# POWER.net
KiCad netlist of a schematic drawn in Altium Designer
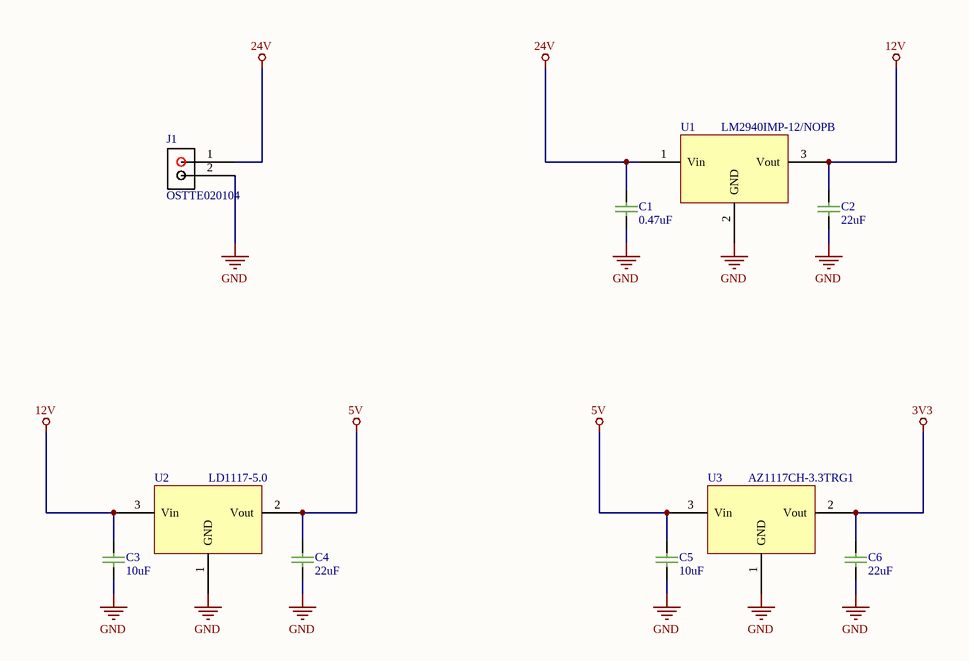
[diagram p0: POWER.SchDoc]

(export (version "E")
  (design (tool "Eeschema 10.0.6"))
  (components
    (comp (ref "C1")
      (value "0.47uF")
      (footprint "CAP-1206")
      (description "CAP CER 0.47UF 50V X7R 1206")
      (libsource (lib "Schlib1") (part "CAP-1206"))
    )
    (comp (ref "C2")
      (value "22uF")
      (footprint "CAP-1206")
      (description "CAP CER 22UF 25V X5R 1206")
      (libsource (lib "Schlib1") (part "CAP-1206"))
    )
    (comp (ref "C3")
      (value "10uF")
      (footprint "CAP-1206")
      (description "CAP CER 10UF 25V X5R 1206")
      (libsource (lib "Schlib1") (part "CAP-1206"))
    )
    (comp (ref "C4")
      (value "22uF")
      (footprint "CAP-1206")
      (description "CAP CER 22UF 16V X5R 1206")
      (libsource (lib "Schlib1") (part "CAP-1206"))
    )
    (comp (ref "C5")
      (value "10uF")
      (footprint "CAP-1206")
      (description "CAP CER 10UF 16V X5R 1206")
      (libsource (lib "Schlib1") (part "CAP-1206"))
    )
    (comp (ref "C6")
      (value "22uF")
      (footprint "CAP-1206")
      (description "CAP CER 22UF 10V X5R 1206")
      (libsource (lib "Schlib1") (part "CAP-1206"))
    )
    (comp (ref "J1")
      (value "OSTTE020104")
      (footprint "TERMBLK-P3.5-SIDEENT")
      (description "TERM BLK 2POS SIDE ENT 3.5MM PCB")
      (libsource (lib "schematic") (part "OSTTE020104"))
    )
    (comp (ref "U1")
      (value "LM2940IMP-12/NOPB")
      (footprint "SOT-223")
      (description "IC REG LINEAR 12V 1A SOT-223-4")
      (libsource (lib "schematic") (part "LM2940IMP-12/NOPB"))
    )
    (comp (ref "U2")
      (value "LD1117-5.0")
      (footprint "SOT-223")
      (description "IC REG LINEAR 5V 1A SOT-223-3L")
      (libsource (lib "schematic") (part "LD1117-5.0"))
    )
    (comp (ref "U3")
      (value "AZ1117CH-3.3TRG1")
      (footprint "SOT-223")
      (description "IC REG LINEAR 3.3V 1A SOT-223-3")
      (libsource (lib "schematic") (part "AZ1117CH-3.3TRG1"))
    )
  )
  (nets
    (net (code "1") (name "3V3") (class "Default")
      (node (ref "C6") (pin "2") (pinfunction "2_2") (pintype "passive"))
      (node (ref "U3") (pin "2") (pinfunction "Vout_2") (pintype "passive"))
    )
    (net (code "2") (name "5V") (class "Default")
      (node (ref "C4") (pin "2") (pinfunction "2_2") (pintype "passive"))
      (node (ref "C5") (pin "2") (pinfunction "2_2") (pintype "passive"))
      (node (ref "U2") (pin "2") (pinfunction "Vout_2") (pintype "passive"))
      (node (ref "U3") (pin "3") (pinfunction "Vin_3") (pintype "passive"))
    )
    (net (code "3") (name "12V") (class "Default")
      (node (ref "C2") (pin "2") (pinfunction "2_2") (pintype "passive"))
      (node (ref "C3") (pin "2") (pinfunction "2_2") (pintype "passive"))
      (node (ref "U1") (pin "3") (pinfunction "Vout_3") (pintype "passive"))
      (node (ref "U2") (pin "3") (pinfunction "Vin_3") (pintype "passive"))
    )
    (net (code "4") (name "24V") (class "Default")
      (node (ref "C1") (pin "2") (pinfunction "2_2") (pintype "passive"))
      (node (ref "J1") (pin "1") (pinfunction "2_1") (pintype "power_in"))
      (node (ref "U1") (pin "1") (pinfunction "Vin_1") (pintype "passive"))
    )
    (net (code "5") (name "GND") (class "Default")
      (node (ref "C1") (pin "1") (pinfunction "1_1") (pintype "passive"))
      (node (ref "C2") (pin "1") (pinfunction "1_1") (pintype "passive"))
      (node (ref "C3") (pin "1") (pinfunction "1_1") (pintype "passive"))
      (node (ref "C4") (pin "1") (pinfunction "1_1") (pintype "passive"))
      (node (ref "C5") (pin "1") (pinfunction "1_1") (pintype "passive"))
      (node (ref "C6") (pin "1") (pinfunction "1_1") (pintype "passive"))
      (node (ref "J1") (pin "2") (pinfunction "2_2") (pintype "passive"))
      (node (ref "U1") (pin "2") (pinfunction "GND_2") (pintype "passive"))
      (node (ref "U2") (pin "1") (pinfunction "GND_1") (pintype "passive"))
      (node (ref "U3") (pin "1") (pinfunction "GND_1") (pintype "passive"))
    )
  )
)
